# yetisponder_vesp02_2_0.net
KiCad netlist of a schematic drawn in EAGLE
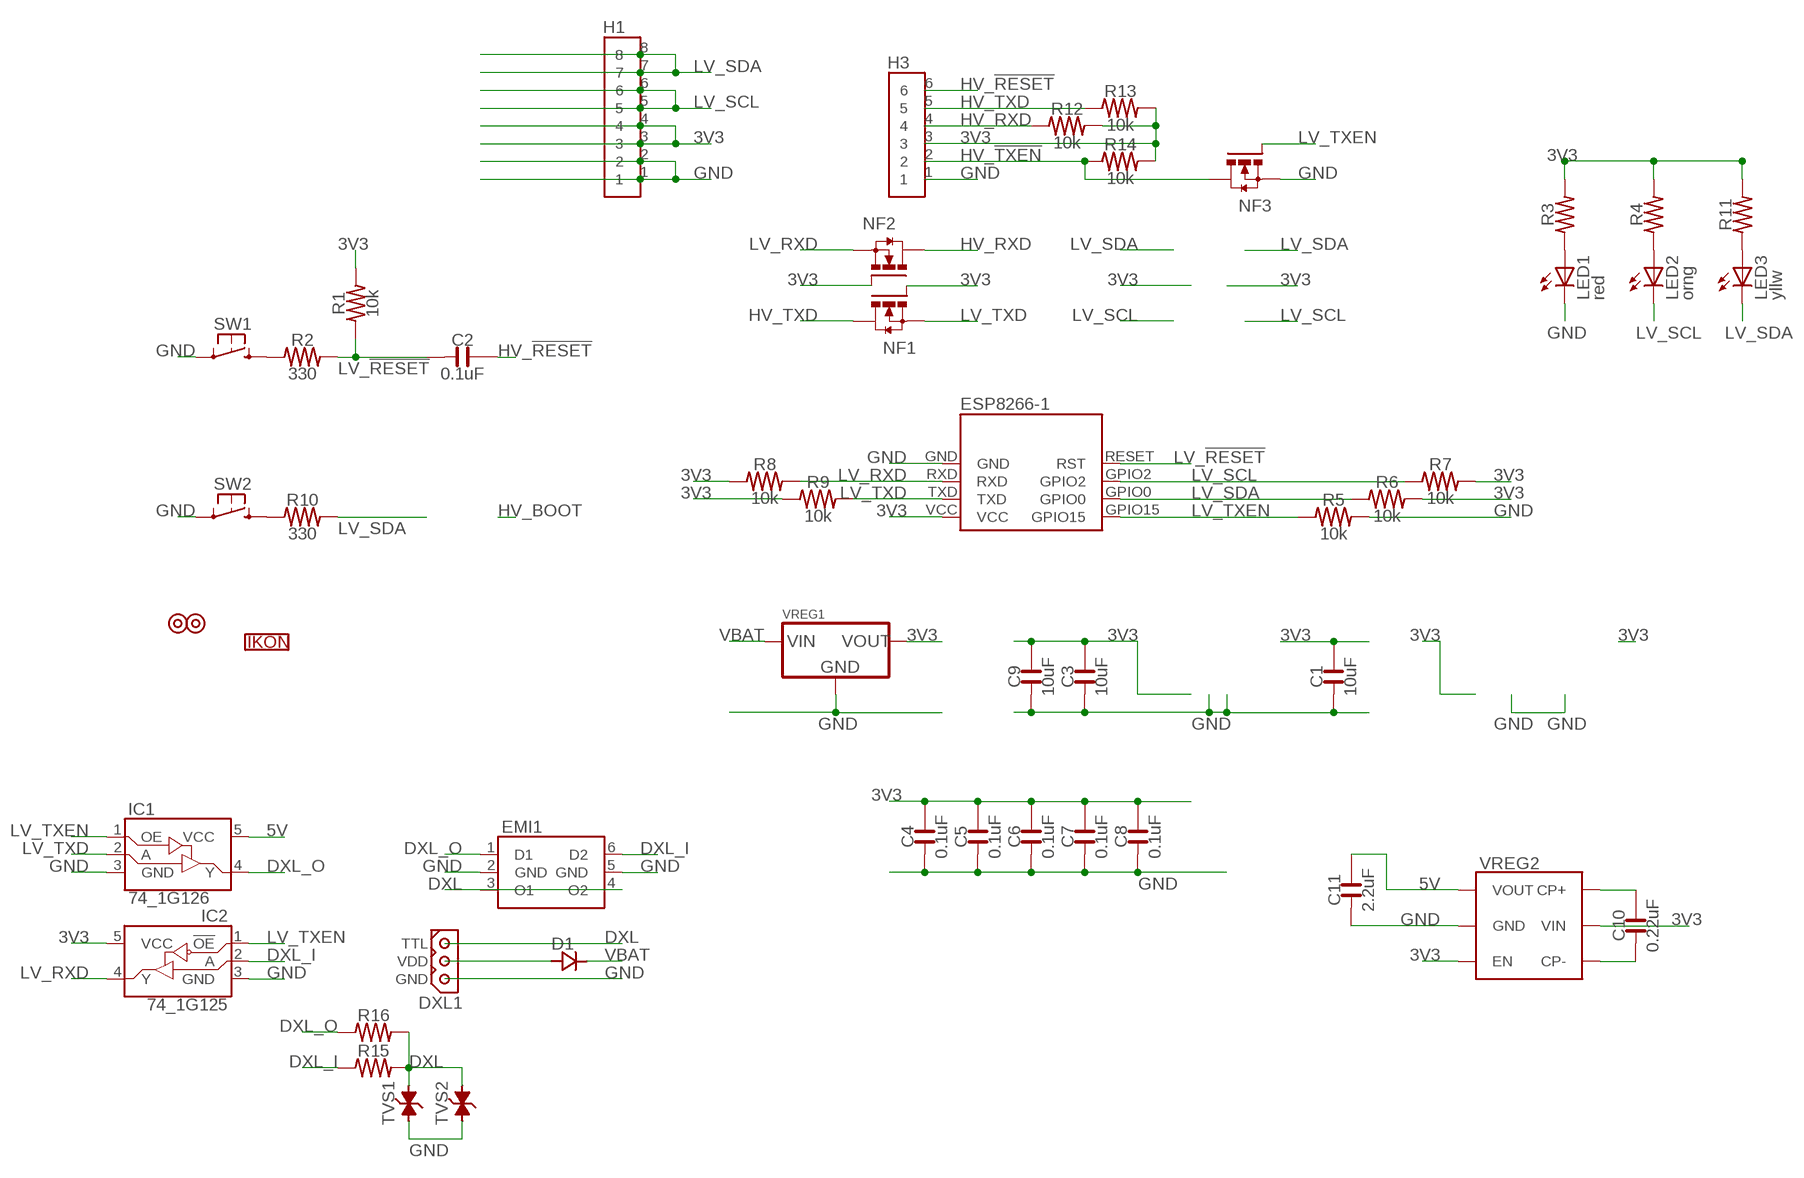
[diagram p0: schematic, sheet 1]

(export (version "E")
  (design (tool "Eeschema 10.0.6"))
  (components
    (comp (ref "C1")
      (value "10uF")
      (footprint "eagle-import:0805_YAGEO")
      (libsource (lib "eagle-import") (part "CAPACITOR-0805"))
    )
    (comp (ref "C2")
      (value "0.1uF")
      (footprint "eagle-import:0402_YAGEO")
      (libsource (lib "eagle-import") (part "CAPACITOR-0402"))
    )
    (comp (ref "C3")
      (value "10uF")
      (footprint "eagle-import:0805_YAGEO")
      (libsource (lib "eagle-import") (part "CAPACITOR-0805"))
    )
    (comp (ref "C4")
      (value "0.1uF")
      (footprint "eagle-import:0402_YAGEO")
      (libsource (lib "eagle-import") (part "CAPACITOR-0402"))
    )
    (comp (ref "C5")
      (value "0.1uF")
      (footprint "eagle-import:0402_YAGEO")
      (libsource (lib "eagle-import") (part "CAPACITOR-0402"))
    )
    (comp (ref "C6")
      (value "0.1uF")
      (footprint "eagle-import:0402_YAGEO")
      (libsource (lib "eagle-import") (part "CAPACITOR-0402"))
    )
    (comp (ref "C7")
      (value "0.1uF")
      (footprint "eagle-import:0402_YAGEO")
      (libsource (lib "eagle-import") (part "CAPACITOR-0402"))
    )
    (comp (ref "C8")
      (value "0.1uF")
      (footprint "eagle-import:0402_YAGEO")
      (libsource (lib "eagle-import") (part "CAPACITOR-0402"))
    )
    (comp (ref "C9")
      (value "10uF")
      (footprint "eagle-import:0805_YAGEO")
      (libsource (lib "eagle-import") (part "CAPACITOR-0805"))
    )
    (comp (ref "C10")
      (value "0.22uF")
      (footprint "eagle-import:0402_YAGEO")
      (libsource (lib "eagle-import") (part "CAPACITOR-0402"))
    )
    (comp (ref "C11")
      (value "2.2uF")
      (footprint "eagle-import:0402_YAGEO")
      (libsource (lib "eagle-import") (part "CAPACITOR-0402"))
    )
    (comp (ref "D1")
      (value "DIODE_RECTIFIER-POWER-DI123")
      (footprint "eagle-import:POWER-DI123")
      (libsource (lib "eagle-import") (part "DIODE_RECTIFIER-POWER-DI123"))
    )
    (comp (ref "DXL1")
      (value "DXL_TTL-V")
      (footprint "eagle-import:MOLEX_5267-3")
      (libsource (lib "eagle-import") (part "DXL_TTL-V"))
    )
    (comp (ref "EMI1")
      (value "EMI_2CH")
      (footprint "eagle-import:SOT-563")
      (libsource (lib "eagle-import") (part "EMI_2CH"))
    )
    (comp (ref "ESP8266-1")
      (value "ESP8266-02")
      (footprint "eagle-import:ESP8266-02")
      (libsource (lib "eagle-import") (part "ESP8266-02"))
    )
    (comp (ref "H1")
      (value "HEADER_8P-0.1\"_2X4-SMD-SULLINS")
      (footprint "eagle-import:HEADER-0.1__2X4-SMD-SULLINS")
      (libsource (lib "eagle-import") (part "HEADER_8P-0.1{dblquote}_2X4-SMD-SULLINS"))
    )
    (comp (ref "H3")
      (value "HEADER_6P-0.1\"")
      (footprint "eagle-import:HEADER-0.1__1X6")
      (libsource (lib "eagle-import") (part "HEADER_6P-0.1{dblquote}"))
    )
    (comp (ref "IC1")
      (value "LOGIC_74_1G126-DCK")
      (footprint "eagle-import:DCK(R-PDSO-G5)_SC70")
      (libsource (lib "eagle-import") (part "LOGIC_74_1G126-DCK"))
    )
    (comp (ref "IC2")
      (value "LOGIC_74_1G125-DCK")
      (footprint "eagle-import:DCK(R-PDSO-G5)_SC70")
      (libsource (lib "eagle-import") (part "LOGIC_74_1G125-DCK"))
    )
    (comp (ref "IKON1")
      (value "IKON-VERSACOMA-5")
      (footprint "eagle-import:IKON_VERSACOMA_5MM")
      (libsource (lib "eagle-import") (part "IKON-VERSACOMA-5"))
    )
    (comp (ref "LED1")
      (value "red")
      (footprint "eagle-import:0402_LED")
      (libsource (lib "eagle-import") (part "LED-0402"))
    )
    (comp (ref "LED2")
      (value "orng")
      (footprint "eagle-import:0402_LED")
      (libsource (lib "eagle-import") (part "LED-0402"))
    )
    (comp (ref "LED3")
      (value "yllw")
      (footprint "eagle-import:0402_LED")
      (libsource (lib "eagle-import") (part "LED-0402"))
    )
    (comp (ref "NF1")
      (value "FET_N-CH-SOT-23-3")
      (footprint "eagle-import:SOT-23-3")
      (libsource (lib "eagle-import") (part "FET_N-CH-SOT-23-3"))
    )
    (comp (ref "NF2")
      (value "FET_N-CH-SOT-23-3")
      (footprint "eagle-import:SOT-23-3")
      (libsource (lib "eagle-import") (part "FET_N-CH-SOT-23-3"))
    )
    (comp (ref "NF3")
      (value "FET_N-CH-SOT-23-3")
      (footprint "eagle-import:SOT-23-3")
      (libsource (lib "eagle-import") (part "FET_N-CH-SOT-23-3"))
    )
    (comp (ref "R1")
      (value "10k")
      (footprint "eagle-import:0402_YAGEO")
      (libsource (lib "eagle-import") (part "RESISTOR-0402"))
    )
    (comp (ref "R2")
      (value "330")
      (footprint "eagle-import:0402_YAGEO")
      (libsource (lib "eagle-import") (part "RESISTOR-0402"))
    )
    (comp (ref "R3")
      (value "RESISTOR-0402")
      (footprint "eagle-import:0402_YAGEO")
      (libsource (lib "eagle-import") (part "RESISTOR-0402"))
    )
    (comp (ref "R4")
      (value "RESISTOR-0402")
      (footprint "eagle-import:0402_YAGEO")
      (libsource (lib "eagle-import") (part "RESISTOR-0402"))
    )
    (comp (ref "R5")
      (value "10k")
      (footprint "eagle-import:0402_YAGEO")
      (libsource (lib "eagle-import") (part "RESISTOR-0402"))
    )
    (comp (ref "R6")
      (value "10k")
      (footprint "eagle-import:0402_YAGEO")
      (libsource (lib "eagle-import") (part "RESISTOR-0402"))
    )
    (comp (ref "R7")
      (value "10k")
      (footprint "eagle-import:0402_YAGEO")
      (libsource (lib "eagle-import") (part "RESISTOR-0402"))
    )
    (comp (ref "R8")
      (value "10k")
      (footprint "eagle-import:0402_YAGEO")
      (libsource (lib "eagle-import") (part "RESISTOR-0402"))
    )
    (comp (ref "R9")
      (value "10k")
      (footprint "eagle-import:0402_YAGEO")
      (libsource (lib "eagle-import") (part "RESISTOR-0402"))
    )
    (comp (ref "R10")
      (value "330")
      (footprint "eagle-import:0402_YAGEO")
      (libsource (lib "eagle-import") (part "RESISTOR-0402"))
    )
    (comp (ref "R11")
      (value "RESISTOR-0402")
      (footprint "eagle-import:0402_YAGEO")
      (libsource (lib "eagle-import") (part "RESISTOR-0402"))
    )
    (comp (ref "R12")
      (value "10k")
      (footprint "eagle-import:0402_YAGEO")
      (libsource (lib "eagle-import") (part "RESISTOR-0402"))
    )
    (comp (ref "R13")
      (value "10k")
      (footprint "eagle-import:0402_YAGEO")
      (libsource (lib "eagle-import") (part "RESISTOR-0402"))
    )
    (comp (ref "R14")
      (value "10k")
      (footprint "eagle-import:0402_YAGEO")
      (libsource (lib "eagle-import") (part "RESISTOR-0402"))
    )
    (comp (ref "R15")
      (value "RESISTOR-0402")
      (footprint "eagle-import:0402_YAGEO")
      (libsource (lib "eagle-import") (part "RESISTOR-0402"))
    )
    (comp (ref "R16")
      (value "RESISTOR-0402")
      (footprint "eagle-import:0402_YAGEO")
      (libsource (lib "eagle-import") (part "RESISTOR-0402"))
    )
    (comp (ref "S1")
      (value "METRIC_SCREWS-M2.5_T")
      (footprint "eagle-import:M2.5_SCREW_TENTED")
      (libsource (lib "eagle-import") (part "METRIC_SCREWS-M2.5_T"))
    )
    (comp (ref "S2")
      (value "METRIC_SCREWS-M2.5_T")
      (footprint "eagle-import:M2.5_SCREW_TENTED")
      (libsource (lib "eagle-import") (part "METRIC_SCREWS-M2.5_T"))
    )
    (comp (ref "SW1")
      (value "SWITCH_SPST-6MMX6MM-PTH")
      (footprint "eagle-import:SWITCH_TE_1825910-7")
      (libsource (lib "eagle-import") (part "SWITCH_SPST-6MMX6MM-PTH"))
    )
    (comp (ref "SW2")
      (value "SWITCH_SPST-6MMX6MM-PTH")
      (footprint "eagle-import:SWITCH_TE_1825910-7")
      (libsource (lib "eagle-import") (part "SWITCH_SPST-6MMX6MM-PTH"))
    )
    (comp (ref "TVS1")
      (value "TVS-0402")
      (footprint "eagle-import:0402_YAGEO")
      (libsource (lib "eagle-import") (part "TVS-0402"))
    )
    (comp (ref "TVS2")
      (value "TVS-0603")
      (footprint "eagle-import:0603_YAGEO")
      (libsource (lib "eagle-import") (part "TVS-0603"))
    )
    (comp (ref "VREG1")
      (value "VREG_78XX-OKI-78SR-H")
      (footprint "eagle-import:VREG-OKI-78SR-H")
      (libsource (lib "eagle-import") (part "VREG_78XX-OKI-78SR-H"))
    )
    (comp (ref "VREG2")
      (value "VREG_REG710XX")
      (footprint "eagle-import:SOT-23-6")
      (libsource (lib "eagle-import") (part "VREG_REG710XX"))
    )
  )
  (nets
    (net (code "1") (name "/3V3") (class "Default")
      (node (ref "C1") (pin "2") (pinfunction "P$2_2") (pintype "passive"))
      (node (ref "C3") (pin "2") (pinfunction "P$2_2") (pintype "passive"))
      (node (ref "C4") (pin "2") (pinfunction "P$2_2") (pintype "passive"))
      (node (ref "C5") (pin "2") (pinfunction "P$2_2") (pintype "passive"))
      (node (ref "C6") (pin "2") (pinfunction "P$2_2") (pintype "passive"))
      (node (ref "C7") (pin "2") (pinfunction "P$2_2") (pintype "passive"))
      (node (ref "C8") (pin "2") (pinfunction "P$2_2") (pintype "passive"))
      (node (ref "C9") (pin "2") (pinfunction "P$2_2") (pintype "passive"))
      (node (ref "ESP8266-1") (pin "VCC") (pinfunction "VCC_VCC") (pintype "bidirectional"))
      (node (ref "H1") (pin "3") (pinfunction "3_3") (pintype "bidirectional"))
      (node (ref "H1") (pin "4") (pinfunction "4_4") (pintype "bidirectional"))
      (node (ref "H3") (pin "3") (pinfunction "3_3") (pintype "bidirectional"))
      (node (ref "IC2") (pin "5") (pinfunction "VCC_5") (pintype "bidirectional"))
      (node (ref "NF1") (pin "1G") (pinfunction "G_1G") (pintype "passive"))
      (node (ref "NF2") (pin "1G") (pinfunction "G_1G") (pintype "passive"))
      (node (ref "R1") (pin "2") (pinfunction "2_2") (pintype "passive"))
      (node (ref "R11") (pin "2") (pinfunction "2_2") (pintype "passive"))
      (node (ref "R12") (pin "2") (pinfunction "2_2") (pintype "passive"))
      (node (ref "R13") (pin "2") (pinfunction "2_2") (pintype "passive"))
      (node (ref "R14") (pin "2") (pinfunction "2_2") (pintype "passive"))
      (node (ref "R3") (pin "2") (pinfunction "2_2") (pintype "passive"))
      (node (ref "R4") (pin "2") (pinfunction "2_2") (pintype "passive"))
      (node (ref "R6") (pin "2") (pinfunction "2_2") (pintype "passive"))
      (node (ref "R7") (pin "2") (pinfunction "2_2") (pintype "passive"))
      (node (ref "R8") (pin "1") (pinfunction "1_1") (pintype "passive"))
      (node (ref "R9") (pin "1") (pinfunction "1_1") (pintype "passive"))
      (node (ref "VREG1") (pin "3") (pinfunction "VOUT_3") (pintype "bidirectional"))
      (node (ref "VREG2") (pin "3") (pinfunction "EN_3") (pintype "bidirectional"))
      (node (ref "VREG2") (pin "5") (pinfunction "VIN_5") (pintype "bidirectional"))
    )
    (net (code "2") (name "/5V") (class "Default")
      (node (ref "C11") (pin "2") (pinfunction "P$2_2") (pintype "passive"))
      (node (ref "IC1") (pin "5") (pinfunction "VCC_5") (pintype "bidirectional"))
      (node (ref "VREG2") (pin "1") (pinfunction "VOUT_1") (pintype "bidirectional"))
    )
    (net (code "3") (name "/DXL") (class "Default")
      (node (ref "DXL1") (pin "1") (pinfunction "TTL_1") (pintype "bidirectional"))
      (node (ref "EMI1") (pin "3") (pinfunction "O1_3") (pintype "bidirectional"))
      (node (ref "EMI1") (pin "4") (pinfunction "O2_4") (pintype "bidirectional"))
      (node (ref "R15") (pin "2") (pinfunction "2_2") (pintype "passive"))
      (node (ref "R16") (pin "2") (pinfunction "2_2") (pintype "passive"))
      (node (ref "TVS1") (pin "2") (pinfunction "P$2_2") (pintype "passive"))
      (node (ref "TVS2") (pin "2") (pinfunction "P$2_2") (pintype "passive"))
    )
    (net (code "4") (name "/DXL_I") (class "Default")
      (node (ref "EMI1") (pin "6") (pinfunction "D2_6") (pintype "bidirectional"))
      (node (ref "IC2") (pin "2") (pinfunction "A_2") (pintype "bidirectional"))
      (node (ref "R15") (pin "1") (pinfunction "1_1") (pintype "passive"))
    )
    (net (code "5") (name "/DXL_O") (class "Default")
      (node (ref "EMI1") (pin "1") (pinfunction "D1_1") (pintype "bidirectional"))
      (node (ref "IC1") (pin "4") (pinfunction "Y_4") (pintype "bidirectional"))
      (node (ref "R16") (pin "1") (pinfunction "1_1") (pintype "passive"))
    )
    (net (code "6") (name "/GND") (class "Default")
      (node (ref "C1") (pin "1") (pinfunction "P$1_1") (pintype "passive"))
      (node (ref "C11") (pin "1") (pinfunction "P$1_1") (pintype "passive"))
      (node (ref "C3") (pin "1") (pinfunction "P$1_1") (pintype "passive"))
      (node (ref "C4") (pin "1") (pinfunction "P$1_1") (pintype "passive"))
      (node (ref "C5") (pin "1") (pinfunction "P$1_1") (pintype "passive"))
      (node (ref "C6") (pin "1") (pinfunction "P$1_1") (pintype "passive"))
      (node (ref "C7") (pin "1") (pinfunction "P$1_1") (pintype "passive"))
      (node (ref "C8") (pin "1") (pinfunction "P$1_1") (pintype "passive"))
      (node (ref "C9") (pin "1") (pinfunction "P$1_1") (pintype "passive"))
      (node (ref "DXL1") (pin "3") (pinfunction "GND_3") (pintype "bidirectional"))
      (node (ref "EMI1") (pin "2") (pinfunction "GND_2") (pintype "bidirectional"))
      (node (ref "EMI1") (pin "5") (pinfunction "GND_5") (pintype "bidirectional"))
      (node (ref "ESP8266-1") (pin "GND") (pinfunction "GND_GND") (pintype "bidirectional"))
      (node (ref "H1") (pin "1") (pinfunction "1_1") (pintype "bidirectional"))
      (node (ref "H1") (pin "2") (pinfunction "2_2") (pintype "bidirectional"))
      (node (ref "H3") (pin "1") (pinfunction "1_1") (pintype "bidirectional"))
      (node (ref "IC1") (pin "3") (pinfunction "GND_3") (pintype "bidirectional"))
      (node (ref "IC2") (pin "3") (pinfunction "GND_3") (pintype "bidirectional"))
      (node (ref "LED1") (pin "C") (pinfunction "C_C") (pintype "passive"))
      (node (ref "NF3") (pin "2S") (pinfunction "S_2S") (pintype "passive"))
      (node (ref "R5") (pin "2") (pinfunction "2_2") (pintype "passive"))
      (node (ref "SW1") (pin "2@1") (pinfunction "2_2@1") (pintype "passive"))
      (node (ref "SW1") (pin "2@2") (pinfunction "2_2@2") (pintype "passive"))
      (node (ref "SW2") (pin "2@1") (pinfunction "2_2@1") (pintype "passive"))
      (node (ref "SW2") (pin "2@2") (pinfunction "2_2@2") (pintype "passive"))
      (node (ref "TVS1") (pin "1") (pinfunction "P$1_1") (pintype "passive"))
      (node (ref "TVS2") (pin "1") (pinfunction "P$1_1") (pintype "passive"))
      (node (ref "VREG1") (pin "2") (pinfunction "GND_2") (pintype "bidirectional"))
      (node (ref "VREG2") (pin "2") (pinfunction "GND_2") (pintype "bidirectional"))
    )
    (net (code "8") (name "/HV_RXD") (class "Default")
      (node (ref "H3") (pin "4") (pinfunction "4_4") (pintype "bidirectional"))
      (node (ref "NF2") (pin "3D") (pinfunction "D_3D") (pintype "passive"))
      (node (ref "R12") (pin "1") (pinfunction "1_1") (pintype "passive"))
    )
    (net (code "9") (name "/HV_TXD") (class "Default")
      (node (ref "H3") (pin "5") (pinfunction "5_5") (pintype "bidirectional"))
      (node (ref "NF1") (pin "3D") (pinfunction "D_3D") (pintype "passive"))
      (node (ref "R13") (pin "1") (pinfunction "1_1") (pintype "passive"))
    )
    (net (code "10") (name "/HV_~{RESET}") (class "Default")
      (node (ref "C2") (pin "2") (pinfunction "P$2_2") (pintype "passive"))
      (node (ref "H3") (pin "6") (pinfunction "6_6") (pintype "bidirectional"))
    )
    (net (code "11") (name "/HV_~{TXEN}") (class "Default")
      (node (ref "H3") (pin "2") (pinfunction "2_2") (pintype "bidirectional"))
      (node (ref "NF3") (pin "3D") (pinfunction "D_3D") (pintype "passive"))
      (node (ref "R14") (pin "1") (pinfunction "1_1") (pintype "passive"))
    )
    (net (code "12") (name "/LV_RXD") (class "Default")
      (node (ref "ESP8266-1") (pin "RXD") (pinfunction "RXD_RXD") (pintype "bidirectional"))
      (node (ref "IC2") (pin "4") (pinfunction "Y_4") (pintype "bidirectional"))
      (node (ref "NF2") (pin "2S") (pinfunction "S_2S") (pintype "passive"))
      (node (ref "R8") (pin "2") (pinfunction "2_2") (pintype "passive"))
    )
    (net (code "13") (name "/LV_SCL") (class "Default")
      (node (ref "ESP8266-1") (pin "GPIO2") (pinfunction "GPIO2_GPIO2") (pintype "bidirectional"))
      (node (ref "H1") (pin "5") (pinfunction "5_5") (pintype "bidirectional"))
      (node (ref "H1") (pin "6") (pinfunction "6_6") (pintype "bidirectional"))
      (node (ref "LED2") (pin "C") (pinfunction "C_C") (pintype "passive"))
      (node (ref "R7") (pin "1") (pinfunction "1_1") (pintype "passive"))
    )
    (net (code "14") (name "/LV_SDA") (class "Default")
      (node (ref "ESP8266-1") (pin "GPIO0") (pinfunction "GPIO0_GPIO0") (pintype "bidirectional"))
      (node (ref "H1") (pin "7") (pinfunction "7_7") (pintype "bidirectional"))
      (node (ref "H1") (pin "8") (pinfunction "8_8") (pintype "bidirectional"))
      (node (ref "LED3") (pin "C") (pinfunction "C_C") (pintype "passive"))
      (node (ref "R10") (pin "2") (pinfunction "2_2") (pintype "passive"))
      (node (ref "R6") (pin "1") (pinfunction "1_1") (pintype "passive"))
    )
    (net (code "15") (name "/LV_TXD") (class "Default")
      (node (ref "ESP8266-1") (pin "TXD") (pinfunction "TXD_TXD") (pintype "bidirectional"))
      (node (ref "IC1") (pin "2") (pinfunction "A_2") (pintype "bidirectional"))
      (node (ref "NF1") (pin "2S") (pinfunction "S_2S") (pintype "passive"))
      (node (ref "R9") (pin "2") (pinfunction "2_2") (pintype "passive"))
    )
    (net (code "16") (name "/LV_TXEN") (class "Default")
      (node (ref "ESP8266-1") (pin "GPIO15") (pinfunction "GPIO15_GPIO15") (pintype "bidirectional"))
      (node (ref "IC1") (pin "1") (pinfunction "OE_1") (pintype "bidirectional"))
      (node (ref "IC2") (pin "1") (pinfunction "~{OE}_1") (pintype "bidirectional"))
      (node (ref "NF3") (pin "1G") (pinfunction "G_1G") (pintype "passive"))
      (node (ref "R5") (pin "1") (pinfunction "1_1") (pintype "passive"))
    )
    (net (code "17") (name "/LV_~{RESET}") (class "Default")
      (node (ref "C2") (pin "1") (pinfunction "P$1_1") (pintype "passive"))
      (node (ref "ESP8266-1") (pin "RESET") (pinfunction "RST_RESET") (pintype "bidirectional"))
      (node (ref "R1") (pin "1") (pinfunction "1_1") (pintype "passive"))
      (node (ref "R2") (pin "2") (pinfunction "2_2") (pintype "passive"))
    )
    (net (code "18") (name "/VBAT") (class "Default")
      (node (ref "D1") (pin "K") (pinfunction "C_K") (pintype "bidirectional"))
      (node (ref "VREG1") (pin "1") (pinfunction "VIN_1") (pintype "bidirectional"))
    )
    (net (code "19") (name "Net-(C10-P$1)") (class "Default")
      (node (ref "C10") (pin "1") (pinfunction "P$1_1") (pintype "passive"))
      (node (ref "VREG2") (pin "4") (pinfunction "CP-_4") (pintype "bidirectional"))
    )
    (net (code "20") (name "Net-(C10-P$2)") (class "Default")
      (node (ref "C10") (pin "2") (pinfunction "P$2_2") (pintype "passive"))
      (node (ref "VREG2") (pin "6") (pinfunction "CP+_6") (pintype "bidirectional"))
    )
    (net (code "21") (name "Net-(DXL1-VDD)") (class "Default")
      (node (ref "D1") (pin "A") (pinfunction "A_A") (pintype "bidirectional"))
      (node (ref "DXL1") (pin "2") (pinfunction "VDD_2") (pintype "bidirectional"))
    )
    (net (code "22") (name "Net-(LED1-PadA)") (class "Default")
      (node (ref "LED1") (pin "A") (pinfunction "A_A") (pintype "passive"))
      (node (ref "R3") (pin "1") (pinfunction "1_1") (pintype "passive"))
    )
    (net (code "23") (name "Net-(LED2-PadA)") (class "Default")
      (node (ref "LED2") (pin "A") (pinfunction "A_A") (pintype "passive"))
      (node (ref "R4") (pin "1") (pinfunction "1_1") (pintype "passive"))
    )
    (net (code "24") (name "Net-(LED3-PadA)") (class "Default")
      (node (ref "LED3") (pin "A") (pinfunction "A_A") (pintype "passive"))
      (node (ref "R11") (pin "1") (pinfunction "1_1") (pintype "passive"))
    )
    (net (code "25") (name "Net-(R2-Pad1)") (class "Default")
      (node (ref "R2") (pin "1") (pinfunction "1_1") (pintype "passive"))
      (node (ref "SW1") (pin "1@1") (pinfunction "1_1@1") (pintype "passive"))
      (node (ref "SW1") (pin "1@2") (pinfunction "1_1@2") (pintype "passive"))
    )
    (net (code "26") (name "Net-(R10-Pad1)") (class "Default")
      (node (ref "R10") (pin "1") (pinfunction "1_1") (pintype "passive"))
      (node (ref "SW2") (pin "1@1") (pinfunction "1_1@1") (pintype "passive"))
      (node (ref "SW2") (pin "1@2") (pinfunction "1_1@2") (pintype "passive"))
    )
    (net (code "27") (name "unconnected-(S1-PadP$1)") (class "Default")
      (node (ref "S1") (pin "P$1") (pinfunction "P$1_P$1") (pintype "passive"))
    )
    (net (code "28") (name "unconnected-(S2-PadP$1)") (class "Default")
      (node (ref "S2") (pin "P$1") (pinfunction "P$1_P$1") (pintype "passive"))
    )
  )
)
